# PowerConnector.net
KiCad netlist of a schematic drawn in Altium Designer
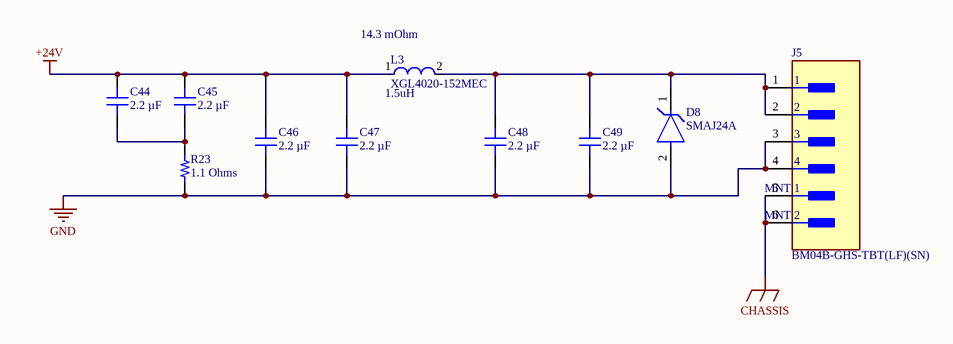
[diagram p0: PowerConnector.SchDoc]

(export (version "E")
  (design (tool "Eeschema 10.0.6"))
  (components
    (comp (ref "C44")
      (value "2.2 µF")
      (footprint "CAP 0805_2012")
      (description "CAP CER 2.2UF 50V X5R 0805")
      (fields
        (field (name "PART NUMBER") "CGA4J3X5R1H225K125AB")
        (field (name "CAPACITANCE") "2.2 µF")
        (field (name "MANUFACTURER") "TDK Corporation")
      )
      (libsource (lib "Celestial Altium Library - altium_library") (part "Capacitor"))
    )
    (comp (ref "C45")
      (value "2.2 µF")
      (footprint "CAP 0805_2012")
      (description "CAP CER 2.2UF 50V X5R 0805")
      (fields
        (field (name "PART NUMBER") "CGA4J3X5R1H225K125AB")
        (field (name "CAPACITANCE") "2.2 µF")
        (field (name "MANUFACTURER") "TDK Corporation")
      )
      (libsource (lib "Celestial Altium Library - altium_library") (part "Capacitor"))
    )
    (comp (ref "C46")
      (value "2.2 µF")
      (footprint "CAP 0805_2012")
      (description "CAP CER 2.2UF 50V X5R 0805")
      (fields
        (field (name "PART NUMBER") "CGA4J3X5R1H225K125AB")
        (field (name "CAPACITANCE") "2.2 µF")
        (field (name "MANUFACTURER") "TDK Corporation")
      )
      (libsource (lib "Celestial Altium Library - altium_library") (part "Capacitor"))
    )
    (comp (ref "C47")
      (value "2.2 µF")
      (footprint "CAP 0805_2012")
      (description "CAP CER 2.2UF 50V X5R 0805")
      (fields
        (field (name "PART NUMBER") "CGA4J3X5R1H225K125AB")
        (field (name "CAPACITANCE") "2.2 µF")
        (field (name "MANUFACTURER") "TDK Corporation")
      )
      (libsource (lib "Celestial Altium Library - altium_library") (part "Capacitor"))
    )
    (comp (ref "C48")
      (value "2.2 µF")
      (footprint "CAP 0805_2012")
      (description "CAP CER 2.2UF 50V X5R 0805")
      (fields
        (field (name "PART NUMBER") "CGA4J3X5R1H225K125AB")
        (field (name "CAPACITANCE") "2.2 µF")
        (field (name "MANUFACTURER") "TDK Corporation")
      )
      (libsource (lib "Celestial Altium Library - altium_library") (part "Capacitor"))
    )
    (comp (ref "C49")
      (value "2.2 µF")
      (footprint "CAP 0805_2012")
      (description "CAP CER 2.2UF 50V X5R 0805")
      (fields
        (field (name "PART NUMBER") "CGA4J3X5R1H225K125AB")
        (field (name "CAPACITANCE") "2.2 µF")
        (field (name "MANUFACTURER") "TDK Corporation")
      )
      (libsource (lib "Celestial Altium Library - altium_library") (part "Capacitor"))
    )
    (comp (ref "D8")
      (value "SMAJ24A")
      (footprint "FP-SMAJ-MFG")
      (description "TVS DIODE 24V 38.9V DO214AC")
      (fields
        (field (name "OCTOPART") "https://octopart.com/smaj24a-littelfuse-350003")
        (field (name "MANUFACTURER") "Littelfuse Inc")
      )
      (libsource (lib "Altium Content Vault") (part "f813f71cba58e380607f5dd3caf9714"))
    )
    (comp (ref "J5")
      (value "BM04B-GHS-TBT(LF)(SN)")
      (footprint "FP-BM04B-GHS-TBT_LF_SN-MFG")
      (description "CONN HEADER SMD 4POS 1.25MM")
      (libsource (lib "Altium Content Vault") (part "8e3688c4b118bffc0dd9b7401e414ba"))
    )
    (comp (ref "L3")
      (value "XGL4020-152MEC")
      (footprint "FP-XGL4020-MFG")
      (description "Shielded Power Inductors")
      (fields
        (field (name "MANUFACTURER") "Coilcraft")
        (field (name "ALTIUM_VALUE") "1.5uH")
        (field (name "TOLERANCE") "20%")
      )
      (libsource (lib "Altium Content Vault") (part "725321dda6339637d4d059423bc1c3c"))
    )
    (comp (ref "R23")
      (value "1.1 Ohms")
      (footprint "RES 0603_1608")
      (description "RES 1.1 OHM 1% 1/5W 0603")
      (fields
        (field (name "PART NUMBER") "SR731JRTTD1R10F")
        (field (name "MANUFACTURER") "KOA Speer Electronics, Inc.")
      )
      (libsource (lib "Celestial Altium Library - altium_library") (part "Resistor"))
    )
  )
  (nets
    (net (code "1") (name "+24V") (class "Default")
      (node (ref "C44") (pin "2") (pinfunction "2_2") (pintype "passive"))
      (node (ref "C45") (pin "2") (pinfunction "2_2") (pintype "passive"))
      (node (ref "C46") (pin "2") (pinfunction "2_2") (pintype "passive"))
      (node (ref "C47") (pin "2") (pinfunction "2_2") (pintype "passive"))
      (node (ref "L3") (pin "1") (pinfunction "1_1") (pintype "passive"))
    )
    (net (code "2") (name "CHASSIS") (class "Default")
      (node (ref "J5") (pin "5") (pinfunction "MNT_1_5") (pintype "passive"))
      (node (ref "J5") (pin "6") (pinfunction "MNT_2_6") (pintype "passive"))
    )
    (net (code "3") (name "GND") (class "Default")
      (node (ref "C46") (pin "1") (pinfunction "1_1") (pintype "passive"))
      (node (ref "C47") (pin "1") (pinfunction "1_1") (pintype "passive"))
      (node (ref "C48") (pin "1") (pinfunction "1_1") (pintype "passive"))
      (node (ref "C49") (pin "1") (pinfunction "1_1") (pintype "passive"))
      (node (ref "D8") (pin "2") (pinfunction "A_2") (pintype "passive"))
      (node (ref "J5") (pin "3") (pinfunction "3_3") (pintype "passive"))
      (node (ref "J5") (pin "4") (pinfunction "4_4") (pintype "passive"))
      (node (ref "R23") (pin "1") (pinfunction "1_1") (pintype "passive"))
    )
    (net (code "4") (name "Net-(C44-Pad1)") (class "Default")
      (node (ref "C44") (pin "1") (pinfunction "1_1") (pintype "passive"))
      (node (ref "C45") (pin "1") (pinfunction "1_1") (pintype "passive"))
      (node (ref "R23") (pin "2") (pinfunction "2_2") (pintype "passive"))
    )
    (net (code "5") (name "Net-(D8-C)") (class "Default")
      (node (ref "C48") (pin "2") (pinfunction "2_2") (pintype "passive"))
      (node (ref "C49") (pin "2") (pinfunction "2_2") (pintype "passive"))
      (node (ref "D8") (pin "1") (pinfunction "C_1") (pintype "passive"))
      (node (ref "J5") (pin "1") (pinfunction "1_1") (pintype "passive"))
      (node (ref "J5") (pin "2") (pinfunction "2_2") (pintype "passive"))
      (node (ref "L3") (pin "2") (pinfunction "2_2") (pintype "passive"))
    )
  )
)
